# VCU_DV.net
KiCad netlist of a schematic drawn in Altium Designer
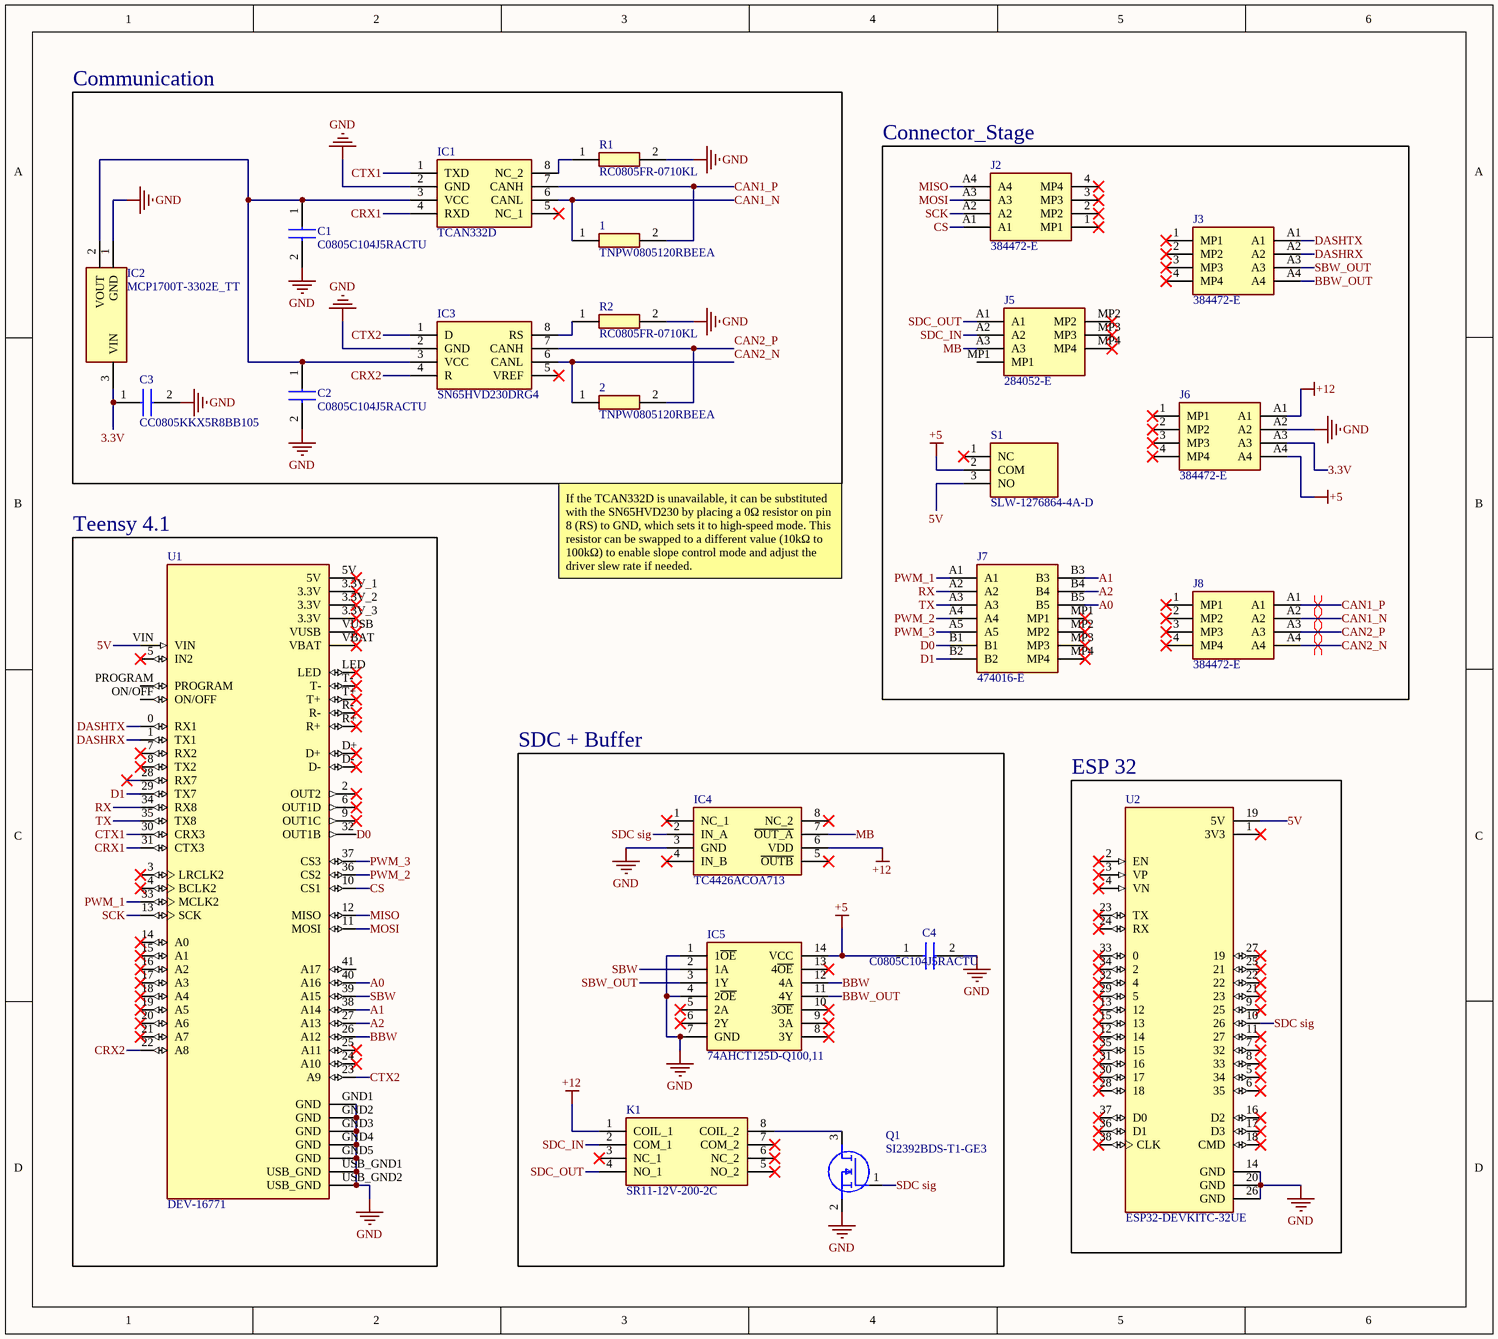
[diagram p0: VCU_DV.SchDoc]

(export (version "E")
  (design (tool "Eeschema 10.0.6"))
  (components
    (comp (ref "1")
      (value "TNPW0805120RBEEA")
      (footprint "SamacSys:RESC2012X55N")
      (description "Resistor")
      (fields (field (name "MOUSER PART NUMBER") "71-TNPW0805120RBEEA"))
      (libsource (lib "*") (part "TNPW0805120RBEEA"))
    )
    (comp (ref "2")
      (value "TNPW0805120RBEEA")
      (footprint "SamacSys:RESC2012X55N")
      (description "Resistor")
      (fields (field (name "MOUSER PART NUMBER") "71-TNPW0805120RBEEA"))
      (libsource (lib "*") (part "TNPW0805120RBEEA"))
    )
    (comp (ref "C1")
      (value "C0805C104J5RACTU")
      (footprint "SamacSys:C0805")
      (description "Capacitor")
      (fields (field (name "MOUSER PART NUMBER") "80-C0805C104J5R"))
      (libsource (lib "*") (part "C0805C104J5RACTU"))
    )
    (comp (ref "C2")
      (value "C0805C104J5RACTU")
      (footprint "SamacSys:C0805")
      (description "Capacitor")
      (fields (field (name "MOUSER PART NUMBER") "80-C0805C104J5R"))
      (libsource (lib "*") (part "C0805C104J5RACTU"))
    )
    (comp (ref "C3")
      (value "CC0805KKX5R8BB105")
      (footprint "SamacSys:CAPC2012X145N")
      (description "Capacitor")
      (fields (field (name "MOUSER PART NUMBER") "603-CC805KKX5R8BB105"))
      (libsource (lib "SamacSys") (part "CC0805KKX5R8BB105"))
    )
    (comp (ref "C4")
      (value "C0805C104J5RACTU")
      (footprint "SamacSys:C0805")
      (description "Capacitor")
      (fields (field (name "MOUSER PART NUMBER") "80-C0805C104J5R"))
      (libsource (lib "*") (part "C0805C104J5RACTU"))
    )
    (comp (ref "IC1")
      (value "TCAN332D")
      (footprint "SamacSys:TCAN332D")
      (description "Integrated Circuit")
      (fields (field (name "MOUSER PART NUMBER") "595-TCAN332D"))
      (libsource (lib "*") (part "TCAN332D"))
    )
    (comp (ref "IC2")
      (value "MCP1700T-3302E_TT")
      (footprint "SamacSys:SOT95P237X112-3N")
      (description "Integrated Circuit")
      (fields
        (field (name "MANUFACTURER_PART_NUMBER") "MCP1700T-3302E/TT")
        (field (name "MOUSER PART NUMBER") "579-MCP1700T3302E/TT")
      )
      (libsource (lib "*") (part "MCP1700T-3302E_TT"))
    )
    (comp (ref "IC3")
      (value "SN65HVD230DRG4")
      (footprint "SamacSys:SOIC127P600X175-8N")
      (description "Integrated Circuit")
      (fields (field (name "MOUSER PART NUMBER") "595-SN65HVD230DRG4"))
      (libsource (lib "*") (part "SN65HVD230DRG4"))
    )
    (comp (ref "IC4")
      (value "TC4426ACOA713")
      (footprint "SamacSys:SOIC127P600X175-8N")
      (description "Integrated Circuit")
      (fields (field (name "MOUSER PART NUMBER") "579-TC4426ACOA713"))
      (libsource (lib "*") (part "TC4426ACOA713"))
    )
    (comp (ref "IC5")
      (value "74AHCT125D-Q100,11")
      (footprint "SamacSys:SOIC127P600X175-14N")
      (description "Integrated Circuit")
      (fields (field (name "MOUSER PART NUMBER") "771-74AHCT100D-Q100"))
      (libsource (lib "*") (part "74AHCT125D-Q100,11"))
    )
    (comp (ref "J2")
      (value "384472-E")
      (footprint "SamacSys:384472E")
      (description "Connector")
      (libsource (lib "") (part "384472-E_1"))
    )
    (comp (ref "J3")
      (value "384472-E")
      (footprint "SamacSys:384472E")
      (description "Connector")
      (libsource (lib "*") (part "384472-E"))
    )
    (comp (ref "J5")
      (value "284052-E")
      (footprint "SamacSys:284052E")
      (description "Connector")
      (fields (field (name "MOUSER PART NUMBER") "305-284052"))
      (libsource (lib "SamacSys") (part "284052-E"))
    )
    (comp (ref "J6")
      (value "384472-E")
      (footprint "SamacSys:384472E")
      (description "Connector")
      (libsource (lib "*") (part "384472-E"))
    )
    (comp (ref "J7")
      (value "474016-E")
      (footprint "SamacSys:474016E")
      (description "Connector")
      (fields (field (name "MOUSER PART NUMBER") "305-474016"))
      (libsource (lib "*") (part "474016-E"))
    )
    (comp (ref "J8")
      (value "384472-E")
      (footprint "SamacSys:384472E")
      (description "Connector")
      (libsource (lib "*") (part "384472-E"))
    )
    (comp (ref "K1")
      (value "SR11-12V-200-2C")
      (footprint "SamacSys:SR1112V2002C")
      (description "Relay or Contactor")
      (fields (field (name "MOUSER PART NUMBER") "179-SR11-12V-200-2C"))
      (libsource (lib "*") (part "SR11-12V-200-2C"))
    )
    (comp (ref "Q1")
      (value "SI2392BDS-T1-GE3")
      (footprint "SamacSys:SOT95P237X112-3N")
      (description "MOSFET (N-Channel)")
      (fields (field (name "MOUSER PART NUMBER") "78-SI2392BDS"))
      (libsource (lib "SamacSys") (part "SI2392BDS-T1-GE3"))
    )
    (comp (ref "R1")
      (value "RC0805FR-0710KL")
      (footprint "SamacSys:RESC2012X60N")
      (description "Resistor")
      (fields (field (name "MOUSER PART NUMBER") "603-RC0805FR-0710KL"))
      (libsource (lib "SamacSys") (part "RC0805FR-0710KL"))
    )
    (comp (ref "R2")
      (value "RC0805FR-0710KL")
      (footprint "SamacSys:RESC2012X60N")
      (description "Resistor")
      (fields (field (name "MOUSER PART NUMBER") "603-RC0805FR-0710KL"))
      (libsource (lib "SamacSys") (part "RC0805FR-0710KL"))
    )
    (comp (ref "S1")
      (value "SLW-1276864-4A-D")
      (footprint "SamacSys:SLW12768644AD")
      (description "Switch")
      (fields (field (name "MOUSER PART NUMBER") "179-SLW-1276864-4A-D"))
      (libsource (lib "*") (part "SLW-1276864-4A-D"))
    )
    (comp (ref "U1")
      (value "DEV-16771")
      (footprint "MODULE_DEV-16771")
      (description "RT1062 Teensy 4.1 series ARM® Cortex®-M7 MPU Embedded Evaluation Board")
      (fields (field (name "MF") "SparkFun Electronics"))
      (libsource (lib "DEV-16771") (part "DEV-16771"))
    )
    (comp (ref "U2")
      (value "ESP32-DEVKITC-32UE")
      (footprint "ESPRESSIF_ESP32-DEVKITC-32UE")
      (fields (field (name "MF") "Espressif Systems"))
      (libsource (lib "ESP32-DEVKITC-32UE") (part "ESP32-DEVKITC-32UE"))
    )
  )
  (nets
    (net (code "1") (name "+5") (class "Default")
      (node (ref "C4") (pin "1") (pinfunction "1_1") (pintype "passive"))
      (node (ref "IC5") (pin "14") (pinfunction "VCC_14") (pintype "passive"))
      (node (ref "J6") (pin "A4") (pinfunction "A4_A4") (pintype "passive"))
      (node (ref "S1") (pin "2") (pinfunction "COM_2") (pintype "passive"))
    )
    (net (code "2") (name "+12") (class "Default")
      (node (ref "IC4") (pin "6") (pinfunction "VDD_6") (pintype "passive"))
      (node (ref "J6") (pin "A1") (pinfunction "A1_A1") (pintype "passive"))
      (node (ref "K1") (pin "1") (pinfunction "COIL_1_1") (pintype "passive"))
    )
    (net (code "3") (name "/3.3V") (class "Default")
      (node (ref "C3") (pin "1") (pinfunction "1_1") (pintype "passive"))
      (node (ref "IC2") (pin "3") (pinfunction "VIN_3") (pintype "passive"))
      (node (ref "J6") (pin "A3") (pinfunction "A3_A3") (pintype "passive"))
    )
    (net (code "4") (name "/5V") (class "Default")
      (node (ref "S1") (pin "3") (pinfunction "NO_3") (pintype "passive"))
      (node (ref "U1") (pin "VIN") (pinfunction "VIN_VIN") (pintype "input"))
      (node (ref "U2") (pin "19") (pinfunction "5V_19") (pintype "power_in"))
    )
    (net (code "5") (name "/A0") (class "Default")
      (node (ref "J7") (pin "B5") (pinfunction "B5_B5") (pintype "passive"))
      (node (ref "U1") (pin "40") (pinfunction "A16_40") (pintype "bidirectional"))
    )
    (net (code "6") (name "/A1") (class "Default")
      (node (ref "J7") (pin "B3") (pinfunction "B3_B3") (pintype "passive"))
      (node (ref "U1") (pin "38") (pinfunction "A14_38") (pintype "bidirectional"))
    )
    (net (code "7") (name "/A2") (class "Default")
      (node (ref "J7") (pin "B4") (pinfunction "B4_B4") (pintype "passive"))
      (node (ref "U1") (pin "27") (pinfunction "A13_27") (pintype "bidirectional"))
    )
    (net (code "8") (name "/BBW") (class "Default")
      (node (ref "IC5") (pin "12") (pinfunction "4A_12") (pintype "passive"))
      (node (ref "U1") (pin "26") (pinfunction "A12_26") (pintype "bidirectional"))
    )
    (net (code "9") (name "/BBW_OUT") (class "Default")
      (node (ref "IC5") (pin "11") (pinfunction "4Y_11") (pintype "passive"))
      (node (ref "J3") (pin "A4") (pinfunction "A4_A4") (pintype "passive"))
    )
    (net (code "10") (name "/CAN1_N") (class "Default")
      (node (ref "1") (pin "1") (pinfunction "1_1") (pintype "passive"))
      (node (ref "IC1") (pin "6") (pinfunction "CANL_6") (pintype "passive"))
      (node (ref "J8") (pin "A2") (pinfunction "A2_A2") (pintype "passive"))
    )
    (net (code "11") (name "/CAN1_P") (class "Default")
      (node (ref "1") (pin "2") (pinfunction "2_2") (pintype "passive"))
      (node (ref "IC1") (pin "7") (pinfunction "CANH_7") (pintype "passive"))
      (node (ref "J8") (pin "A1") (pinfunction "A1_A1") (pintype "passive"))
    )
    (net (code "12") (name "/CAN2_N") (class "Default")
      (node (ref "2") (pin "1") (pinfunction "1_1") (pintype "passive"))
      (node (ref "IC3") (pin "6") (pinfunction "CANL_6") (pintype "passive"))
      (node (ref "J8") (pin "A4") (pinfunction "A4_A4") (pintype "passive"))
    )
    (net (code "13") (name "/CAN2_P") (class "Default")
      (node (ref "2") (pin "2") (pinfunction "2_2") (pintype "passive"))
      (node (ref "IC3") (pin "7") (pinfunction "CANH_7") (pintype "passive"))
      (node (ref "J8") (pin "A3") (pinfunction "A3_A3") (pintype "passive"))
    )
    (net (code "14") (name "/CRX1") (class "Default")
      (node (ref "IC1") (pin "4") (pinfunction "RXD_4") (pintype "passive"))
      (node (ref "U1") (pin "31") (pinfunction "CTX3_31") (pintype "bidirectional"))
    )
    (net (code "15") (name "/CRX2") (class "Default")
      (node (ref "IC3") (pin "4") (pinfunction "R_4") (pintype "passive"))
      (node (ref "U1") (pin "22") (pinfunction "A8_22") (pintype "bidirectional"))
    )
    (net (code "16") (name "/CS") (class "Default")
      (node (ref "J2") (pin "A1") (pinfunction "A1_A1") (pintype "passive"))
      (node (ref "U1") (pin "10") (pinfunction "CS1_10") (pintype "bidirectional"))
    )
    (net (code "17") (name "/CTX1") (class "Default")
      (node (ref "IC1") (pin "1") (pinfunction "TXD_1") (pintype "passive"))
      (node (ref "U1") (pin "30") (pinfunction "CRX3_30") (pintype "bidirectional"))
    )
    (net (code "18") (name "/CTX2") (class "Default")
      (node (ref "IC3") (pin "1") (pinfunction "D_1") (pintype "passive"))
      (node (ref "U1") (pin "23") (pinfunction "A9_23") (pintype "bidirectional"))
    )
    (net (code "19") (name "/D0") (class "Default")
      (node (ref "J7") (pin "B1") (pinfunction "B1_B1") (pintype "passive"))
      (node (ref "U1") (pin "32") (pinfunction "OUT1B_32") (pintype "output"))
    )
    (net (code "20") (name "/D1") (class "Default")
      (node (ref "J7") (pin "B2") (pinfunction "B2_B2") (pintype "passive"))
      (node (ref "U1") (pin "29") (pinfunction "TX7_29") (pintype "bidirectional"))
    )
    (net (code "21") (name "/DASHRX") (class "Default")
      (node (ref "J3") (pin "A2") (pinfunction "A2_A2") (pintype "passive"))
      (node (ref "U1") (pin "1") (pinfunction "TX1_1") (pintype "bidirectional"))
    )
    (net (code "22") (name "/DASHTX") (class "Default")
      (node (ref "J3") (pin "A1") (pinfunction "A1_A1") (pintype "passive"))
      (node (ref "U1") (pin "0") (pinfunction "RX1_0") (pintype "bidirectional"))
    )
    (net (code "23") (name "/MB") (class "Default")
      (node (ref "IC4") (pin "7") (pinfunction "~{OUT_A}_7") (pintype "passive"))
      (node (ref "J5") (pin "A3") (pinfunction "A3_A3") (pintype "passive"))
    )
    (net (code "24") (name "/MISO") (class "Default")
      (node (ref "J2") (pin "A4") (pinfunction "A4_A4") (pintype "passive"))
      (node (ref "U1") (pin "12") (pinfunction "MISO_12") (pintype "bidirectional"))
    )
    (net (code "25") (name "/MOSI") (class "Default")
      (node (ref "J2") (pin "A3") (pinfunction "A3_A3") (pintype "passive"))
      (node (ref "U1") (pin "11") (pinfunction "MOSI_11") (pintype "bidirectional"))
    )
    (net (code "26") (name "/PWM_1") (class "Default")
      (node (ref "J7") (pin "A1") (pinfunction "A1_A1") (pintype "passive"))
      (node (ref "U1") (pin "33") (pinfunction "MCLK2_33") (pintype "bidirectional"))
    )
    (net (code "27") (name "/PWM_2") (class "Default")
      (node (ref "J7") (pin "A4") (pinfunction "A4_A4") (pintype "passive"))
      (node (ref "U1") (pin "36") (pinfunction "CS2_36") (pintype "bidirectional"))
    )
    (net (code "28") (name "/PWM_3") (class "Default")
      (node (ref "J7") (pin "A5") (pinfunction "A5_A5") (pintype "passive"))
      (node (ref "U1") (pin "37") (pinfunction "CS3_37") (pintype "bidirectional"))
    )
    (net (code "29") (name "/RX") (class "Default")
      (node (ref "J7") (pin "A2") (pinfunction "A2_A2") (pintype "passive"))
      (node (ref "U1") (pin "34") (pinfunction "RX8_34") (pintype "bidirectional"))
    )
    (net (code "30") (name "/SBW") (class "Default")
      (node (ref "IC5") (pin "2") (pinfunction "1A_2") (pintype "passive"))
      (node (ref "U1") (pin "39") (pinfunction "A15_39") (pintype "bidirectional"))
    )
    (net (code "31") (name "/SBW_OUT") (class "Default")
      (node (ref "IC5") (pin "3") (pinfunction "1Y_3") (pintype "passive"))
      (node (ref "J3") (pin "A3") (pinfunction "A3_A3") (pintype "passive"))
    )
    (net (code "32") (name "/SCK") (class "Default")
      (node (ref "J2") (pin "A2") (pinfunction "A2_A2") (pintype "passive"))
      (node (ref "U1") (pin "13") (pinfunction "SCK_13") (pintype "bidirectional"))
    )
    (net (code "33") (name "/SDC sig") (class "Default")
      (node (ref "IC4") (pin "2") (pinfunction "IN_A_2") (pintype "passive"))
      (node (ref "Q1") (pin "1") (pinfunction "G_1") (pintype "passive"))
      (node (ref "U2") (pin "10") (pinfunction "26_10") (pintype "bidirectional"))
    )
    (net (code "34") (name "/SDC_IN") (class "Default")
      (node (ref "J5") (pin "A2") (pinfunction "A2_A2") (pintype "passive"))
      (node (ref "K1") (pin "2") (pinfunction "COM_1_2") (pintype "passive"))
    )
    (net (code "35") (name "/SDC_OUT") (class "Default")
      (node (ref "J5") (pin "A1") (pinfunction "A1_A1") (pintype "passive"))
      (node (ref "K1") (pin "4") (pinfunction "NO_1_4") (pintype "passive"))
    )
    (net (code "36") (name "/TX") (class "Default")
      (node (ref "J7") (pin "A3") (pinfunction "A3_A3") (pintype "passive"))
      (node (ref "U1") (pin "35") (pinfunction "TX8_35") (pintype "bidirectional"))
    )
    (net (code "37") (name "GND") (class "Default")
      (node (ref "C1") (pin "2") (pinfunction "2_2") (pintype "passive"))
      (node (ref "C2") (pin "2") (pinfunction "2_2") (pintype "passive"))
      (node (ref "C3") (pin "2") (pinfunction "2_2") (pintype "passive"))
      (node (ref "C4") (pin "2") (pinfunction "2_2") (pintype "passive"))
      (node (ref "IC1") (pin "2") (pinfunction "GND_2") (pintype "passive"))
      (node (ref "IC2") (pin "1") (pinfunction "GND_1") (pintype "passive"))
      (node (ref "IC3") (pin "2") (pinfunction "GND_2") (pintype "passive"))
      (node (ref "IC4") (pin "3") (pinfunction "GND_3") (pintype "passive"))
      (node (ref "IC5") (pin "1") (pinfunction "1~{OE}_1") (pintype "passive"))
      (node (ref "IC5") (pin "4") (pinfunction "2~{OE}_4") (pintype "passive"))
      (node (ref "IC5") (pin "7") (pinfunction "GND_7") (pintype "passive"))
      (node (ref "J6") (pin "A2") (pinfunction "A2_A2") (pintype "passive"))
      (node (ref "Q1") (pin "2") (pinfunction "S_2") (pintype "passive"))
      (node (ref "R1") (pin "2") (pinfunction "2_2") (pintype "passive"))
      (node (ref "R2") (pin "2") (pinfunction "2_2") (pintype "passive"))
      (node (ref "U1") (pin "GND1") (pinfunction "GND_GND1") (pintype "power_in"))
      (node (ref "U1") (pin "GND2") (pinfunction "GND_GND2") (pintype "power_in"))
      (node (ref "U1") (pin "GND3") (pinfunction "GND_GND3") (pintype "power_in"))
      (node (ref "U1") (pin "GND4") (pinfunction "GND_GND4") (pintype "power_in"))
      (node (ref "U1") (pin "GND5") (pinfunction "GND_GND5") (pintype "power_in"))
      (node (ref "U1") (pin "USB_GND1") (pinfunction "USB_GND_USB_GND1") (pintype "power_in"))
      (node (ref "U1") (pin "USB_GND2") (pinfunction "USB_GND_USB_GND2") (pintype "power_in"))
      (node (ref "U2") (pin "14") (pinfunction "GND_14") (pintype "power_in"))
      (node (ref "U2") (pin "20") (pinfunction "GND_20") (pintype "power_in"))
      (node (ref "U2") (pin "26") (pinfunction "GND_26") (pintype "power_in"))
    )
    (net (code "38") (name "Net-(IC1-NC_2)") (class "Default")
      (node (ref "IC1") (pin "8") (pinfunction "NC_2_8") (pintype "passive"))
      (node (ref "R1") (pin "1") (pinfunction "1_1") (pintype "passive"))
    )
    (net (code "39") (name "Net-(IC1-VCC)") (class "Default")
      (node (ref "C1") (pin "1") (pinfunction "1_1") (pintype "passive"))
      (node (ref "C2") (pin "1") (pinfunction "1_1") (pintype "passive"))
      (node (ref "IC1") (pin "3") (pinfunction "VCC_3") (pintype "passive"))
      (node (ref "IC2") (pin "2") (pinfunction "VOUT_2") (pintype "passive"))
      (node (ref "IC3") (pin "3") (pinfunction "VCC_3") (pintype "passive"))
    )
    (net (code "40") (name "Net-(IC3-RS)") (class "Default")
      (node (ref "IC3") (pin "8") (pinfunction "RS_8") (pintype "passive"))
      (node (ref "R2") (pin "1") (pinfunction "1_1") (pintype "passive"))
    )
    (net (code "41") (name "Net-(K1-COIL_2)") (class "Default")
      (node (ref "K1") (pin "8") (pinfunction "COIL_2_8") (pintype "passive"))
      (node (ref "Q1") (pin "3") (pinfunction "D_3") (pintype "passive"))
    )
    (net (code "42") (name "unconnected-(IC1-NC_1-Pad5)") (class "Default")
      (node (ref "IC1") (pin "5") (pinfunction "NC_1_5") (pintype "passive+no_connect"))
    )
    (net (code "43") (name "unconnected-(IC3-VREF-Pad5)") (class "Default")
      (node (ref "IC3") (pin "5") (pinfunction "VREF_5") (pintype "passive+no_connect"))
    )
    (net (code "44") (name "unconnected-(IC4-IN_B-Pad4)") (class "Default")
      (node (ref "IC4") (pin "4") (pinfunction "IN_B_4") (pintype "passive+no_connect"))
    )
    (net (code "45") (name "unconnected-(IC4-NC_1-Pad1)") (class "Default")
      (node (ref "IC4") (pin "1") (pinfunction "NC_1_1") (pintype "passive+no_connect"))
    )
    (net (code "46") (name "unconnected-(IC4-NC_2-Pad8)") (class "Default")
      (node (ref "IC4") (pin "8") (pinfunction "NC_2_8") (pintype "passive+no_connect"))
    )
    (net (code "47") (name "unconnected-(IC4-~{OUTB}-Pad5)") (class "Default")
      (node (ref "IC4") (pin "5") (pinfunction "~{OUTB}_5") (pintype "passive+no_connect"))
    )
    (net (code "48") (name "unconnected-(IC5-2A-Pad5)") (class "Default")
      (node (ref "IC5") (pin "5") (pinfunction "2A_5") (pintype "passive+no_connect"))
    )
    (net (code "49") (name "unconnected-(IC5-2Y-Pad6)") (class "Default")
      (node (ref "IC5") (pin "6") (pinfunction "2Y_6") (pintype "passive+no_connect"))
    )
    (net (code "50") (name "unconnected-(IC5-3A-Pad9)") (class "Default")
      (node (ref "IC5") (pin "9") (pinfunction "3A_9") (pintype "passive+no_connect"))
    )
    (net (code "51") (name "unconnected-(IC5-3Y-Pad8)") (class "Default")
      (node (ref "IC5") (pin "8") (pinfunction "3Y_8") (pintype "passive+no_connect"))
    )
    (net (code "52") (name "unconnected-(IC5-3~{OE}-Pad10)") (class "Default")
      (node (ref "IC5") (pin "10") (pinfunction "3~{OE}_10") (pintype "passive+no_connect"))
    )
    (net (code "53") (name "unconnected-(IC5-4~{OE}-Pad13)") (class "Default")
      (node (ref "IC5") (pin "13") (pinfunction "4~{OE}_13") (pintype "passive+no_connect"))
    )
    (net (code "54") (name "unconnected-(J2-MP1-Pad1)") (class "Default")
      (node (ref "J2") (pin "1") (pinfunction "MP1_1") (pintype "passive+no_connect"))
    )
    (net (code "55") (name "unconnected-(J2-MP2-Pad2)") (class "Default")
      (node (ref "J2") (pin "2") (pinfunction "MP2_2") (pintype "passive+no_connect"))
    )
    (net (code "56") (name "unconnected-(J2-MP3-Pad3)") (class "Default")
      (node (ref "J2") (pin "3") (pinfunction "MP3_3") (pintype "passive+no_connect"))
    )
    (net (code "57") (name "unconnected-(J2-MP4-Pad4)") (class "Default")
      (node (ref "J2") (pin "4") (pinfunction "MP4_4") (pintype "passive+no_connect"))
    )
    (net (code "58") (name "unconnected-(J3-MP1-Pad1)") (class "Default")
      (node (ref "J3") (pin "1") (pinfunction "MP1_1") (pintype "passive+no_connect"))
    )
    (net (code "59") (name "unconnected-(J3-MP2-Pad2)") (class "Default")
      (node (ref "J3") (pin "2") (pinfunction "MP2_2") (pintype "passive+no_connect"))
    )
    (net (code "60") (name "unconnected-(J3-MP3-Pad3)") (class "Default")
      (node (ref "J3") (pin "3") (pinfunction "MP3_3") (pintype "passive+no_connect"))
    )
    (net (code "61") (name "unconnected-(J3-MP4-Pad4)") (class "Default")
      (node (ref "J3") (pin "4") (pinfunction "MP4_4") (pintype "passive+no_connect"))
    )
    (net (code "62") (name "unconnected-(J5-PadMP1)") (class "Default")
      (node (ref "J5") (pin "MP1") (pinfunction "MP1_MP1") (pintype "passive"))
    )
    (net (code "63") (name "unconnected-(J5-PadMP2)") (class "Default")
      (node (ref "J5") (pin "MP2") (pinfunction "MP2_MP2") (pintype "passive+no_connect"))
    )
    (net (code "64") (name "unconnected-(J5-PadMP3)") (class "Default")
      (node (ref "J5") (pin "MP3") (pinfunction "MP3_MP3") (pintype "passive+no_connect"))
    )
    (net (code "65") (name "unconnected-(J5-PadMP4)") (class "Default")
      (node (ref "J5") (pin "MP4") (pinfunction "MP4_MP4") (pintype "passive+no_connect"))
    )
    (net (code "66") (name "unconnected-(J6-MP1-Pad1)") (class "Default")
      (node (ref "J6") (pin "1") (pinfunction "MP1_1") (pintype "passive+no_connect"))
    )
    (net (code "67") (name "unconnected-(J6-MP2-Pad2)") (class "Default")
      (node (ref "J6") (pin "2") (pinfunction "MP2_2") (pintype "passive+no_connect"))
    )
    (net (code "68") (name "unconnected-(J6-MP3-Pad3)") (class "Default")
      (node (ref "J6") (pin "3") (pinfunction "MP3_3") (pintype "passive+no_connect"))
    )
    (net (code "69") (name "unconnected-(J6-MP4-Pad4)") (class "Default")
      (node (ref "J6") (pin "4") (pinfunction "MP4_4") (pintype "passive+no_connect"))
    )
    (net (code "70") (name "unconnected-(J7-PadMP1)") (class "Default")
      (node (ref "J7") (pin "MP1") (pinfunction "MP1_MP1") (pintype "passive+no_connect"))
    )
    (net (code "71") (name "unconnected-(J7-PadMP2)") (class "Default")
      (node (ref "J7") (pin "MP2") (pinfunction "MP2_MP2") (pintype "passive+no_connect"))
    )
    (net (code "72") (name "unconnected-(J7-PadMP3)") (class "Default")
      (node (ref "J7") (pin "MP3") (pinfunction "MP3_MP3") (pintype "passive+no_connect"))
    )
    (net (code "73") (name "unconnected-(J7-PadMP4)") (class "Default")
      (node (ref "J7") (pin "MP4") (pinfunction "MP4_MP4") (pintype "passive+no_connect"))
    )
    (net (code "74") (name "unconnected-(J8-MP1-Pad1)") (class "Default")
      (node (ref "J8") (pin "1") (pinfunction "MP1_1") (pintype "passive+no_connect"))
    )
    (net (code "75") (name "unconnected-(J8-MP2-Pad2)") (class "Default")
      (node (ref "J8") (pin "2") (pinfunction "MP2_2") (pintype "passive+no_connect"))
    )
    (net (code "76") (name "unconnected-(J8-MP3-Pad3)") (class "Default")
      (node (ref "J8") (pin "3") (pinfunction "MP3_3") (pintype "passive+no_connect"))
    )
    (net (code "77") (name "unconnected-(J8-MP4-Pad4)") (class "Default")
      (node (ref "J8") (pin "4") (pinfunction "MP4_4") (pintype "passive+no_connect"))
    )
    (net (code "78") (name "unconnected-(K1-COM_2-Pad7)") (class "Default")
      (node (ref "K1") (pin "7") (pinfunction "COM_2_7") (pintype "passive+no_connect"))
    )
    (net (code "79") (name "unconnected-(K1-NC_1-Pad3)") (class "Default")
      (node (ref "K1") (pin "3") (pinfunction "NC_1_3") (pintype "passive+no_connect"))
    )
    (net (code "80") (name "unconnected-(K1-NC_2-Pad6)") (class "Default")
      (node (ref "K1") (pin "6") (pinfunction "NC_2_6") (pintype "passive+no_connect"))
    )
    (net (code "81") (name "unconnected-(K1-NO_2-Pad5)") (class "Default")
      (node (ref "K1") (pin "5") (pinfunction "NO_2_5") (pintype "passive+no_connect"))
    )
    (net (code "82") (name "unconnected-(S1-NC-Pad1)") (class "Default")
      (node (ref "S1") (pin "1") (pinfunction "NC_1") (pintype "passive+no_connect"))
    )
    (net (code "83") (name "unconnected-(U1-3.3V-Pad3.3V_1)") (class "Default")
      (node (ref "U1") (pin "3.3V_1") (pinfunction "3.3V_3.3V_1") (pintype "power_in+no_connect"))
    )
    (net (code "84") (name "unconnected-(U1-3.3V-Pad3.3V_2)") (class "Default")
      (node (ref "U1") (pin "3.3V_2") (pinfunction "3.3V_3.3V_2") (pintype "power_in+no_connect"))
    )
    (net (code "85") (name "unconnected-(U1-3.3V-Pad3.3V_3)") (class "Default")
      (node (ref "U1") (pin "3.3V_3") (pinfunction "3.3V_3.3V_3") (pintype "power_in+no_connect"))
    )
    (net (code "86") (name "unconnected-(U1-A0-Pad14)") (class "Default")
      (node (ref "U1") (pin "14") (pinfunction "A0_14") (pintype "bidirectional+no_connect"))
    )
    (net (code "87") (name "unconnected-(U1-A1-Pad15)") (class "Default")
      (node (ref "U1") (pin "15") (pinfunction "A1_15") (pintype "bidirectional+no_connect"))
    )
    (net (code "88") (name "unconnected-(U1-A2-Pad16)") (class "Default")
      (node (ref "U1") (pin "16") (pinfunction "A2_16") (pintype "bidirectional+no_connect"))
    )
    (net (code "89") (name "unconnected-(U1-A3-Pad17)") (class "Default")
      (node (ref "U1") (pin "17") (pinfunction "A3_17") (pintype "bidirectional+no_connect"))
    )
    (net (code "90") (name "unconnected-(U1-A4-Pad18)") (class "Default")
      (node (ref "U1") (pin "18") (pinfunction "A4_18") (pintype "bidirectional+no_connect"))
    )
    (net (code "91") (name "unconnected-(U1-A5-Pad19)") (class "Default")
      (node (ref "U1") (pin "19") (pinfunction "A5_19") (pintype "bidirectional+no_connect"))
    )
    (net (code "92") (name "unconnected-(U1-A6-Pad20)") (class "Default")
      (node (ref "U1") (pin "20") (pinfunction "A6_20") (pintype "bidirectional+no_connect"))
    )
    (net (code "93") (name "unconnected-(U1-A7-Pad21)") (class "Default")
      (node (ref "U1") (pin "21") (pinfunction "A7_21") (pintype "bidirectional+no_connect"))
    )
    (net (code "94") (name "unconnected-(U1-A10-Pad24)") (class "Default")
      (node (ref "U1") (pin "24") (pinfunction "A10_24") (pintype "bidirectional+no_connect"))
    )
    (net (code "95") (name "unconnected-(U1-A11-Pad25)") (class "Default")
      (node (ref "U1") (pin "25") (pinfunction "A11_25") (pintype "bidirectional+no_connect"))
    )
    (net (code "96") (name "unconnected-(U1-A17-Pad41)") (class "Default")
      (node (ref "U1") (pin "41") (pinfunction "A17_41") (pintype "bidirectional"))
    )
    (net (code "97") (name "unconnected-(U1-BCLK2-Pad4)") (class "Default")
      (node (ref "U1") (pin "4") (pinfunction "BCLK2_4") (pintype "bidirectional+no_connect"))
    )
    (net (code "98") (name "unconnected-(U1-IN2-Pad5)") (class "Default")
      (node (ref "U1") (pin "5") (pinfunction "IN2_5") (pintype "bidirectional+no_connect"))
    )
    (net (code "99") (name "unconnected-(U1-LRCLK2-Pad3)") (class "Default")
      (node (ref "U1") (pin "3") (pinfunction "LRCLK2_3") (pintype "bidirectional+no_connect"))
    )
    (net (code "100") (name "unconnected-(U1-OUT1C-Pad9)") (class "Default")
      (node (ref "U1") (pin "9") (pinfunction "OUT1C_9") (pintype "output+no_connect"))
    )
    (net (code "101") (name "unconnected-(U1-OUT1D-Pad6)") (class "Default")
      (node (ref "U1") (pin "6") (pinfunction "OUT1D_6") (pintype "output+no_connect"))
    )
    (net (code "102") (name "unconnected-(U1-OUT2-Pad2)") (class "Default")
      (node (ref "U1") (pin "2") (pinfunction "OUT2_2") (pintype "output+no_connect"))
    )
    (net (code "103") (name "unconnected-(U1-Pad5V)") (class "Default")
      (node (ref "U1") (pin "5V") (pinfunction "5V_5V") (pintype "power_in+no_connect"))
    )
    (net (code "104") (name "unconnected-(U1-PadD+)") (class "Default")
      (node (ref "U1") (pin "D+") (pinfunction "D+_D+") (pintype "bidirectional+no_connect"))
    )
    (net (code "105") (name "unconnected-(U1-PadD-)") (class "Default")
      (node (ref "U1") (pin "D-") (pinfunction "D-_D-") (pintype "bidirectional+no_connect"))
    )
    (net (code "106") (name "unconnected-(U1-PadLED)") (class "Default")
      (node (ref "U1") (pin "LED") (pinfunction "LED_LED") (pintype "bidirectional+no_connect"))
    )
    (net (code "107") (name "unconnected-(U1-PadON{slash}OFF)") (class "Default")
      (node (ref "U1") (pin "ON/OFF") (pinfunction "ON/OFF_ON/OFF") (pintype "bidirectional"))
    )
    (net (code "108") (name "unconnected-(U1-PadPROGRAM)") (class "Default")
      (node (ref "U1") (pin "PROGRAM") (pinfunction "PROGRAM_PROGRAM") (pintype "bidirectional"))
    )
    (net (code "109") (name "unconnected-(U1-PadR+)") (class "Default")
      (node (ref "U1") (pin "R+") (pinfunction "R+_R+") (pintype "bidirectional+no_connect"))
    )
    (net (code "110") (name "unconnected-(U1-PadR-)") (class "Default")
      (node (ref "U1") (pin "R-") (pinfunction "R-_R-") (pintype "bidirectional+no_connect"))
    )
    (net (code "111") (name "unconnected-(U1-PadT+)") (class "Default")
      (node (ref "U1") (pin "T+") (pinfunction "T+_T+") (pintype "bidirectional+no_connect"))
    )
    (net (code "112") (name "unconnected-(U1-PadT-)") (class "Default")
      (node (ref "U1") (pin "T-") (pinfunction "T-_T-") (pintype "bidirectional+no_connect"))
    )
    (net (code "113") (name "unconnected-(U1-PadVBAT)") (class "Default")
      (node (ref "U1") (pin "VBAT") (pinfunction "VBAT_VBAT") (pintype "passive+no_connect"))
    )
    (net (code "114") (name "unconnected-(U1-PadVUSB)") (class "Default")
      (node (ref "U1") (pin "VUSB") (pinfunction "VUSB_VUSB") (pintype "passive+no_connect"))
    )
    (net (code "115") (name "unconnected-(U1-RX2-Pad7)") (class "Default")
      (node (ref "U1") (pin "7") (pinfunction "RX2_7") (pintype "bidirectional+no_connect"))
    )
    (net (code "116") (name "unconnected-(U1-RX7-Pad28)") (class "Default")
      (node (ref "U1") (pin "28") (pinfunction "RX7_28") (pintype "bidirectional+no_connect"))
    )
    (net (code "117") (name "unconnected-(U1-TX2-Pad8)") (class "Default")
      (node (ref "U1") (pin "8") (pinfunction "TX2_8") (pintype "bidirectional+no_connect"))
    )
    (net (code "118") (name "unconnected-(U2-0-Pad33)") (class "Default")
      (node (ref "U2") (pin "33") (pinfunction "0_33") (pintype "bidirectional+no_connect"))
    )
    (net (code "119") (name "unconnected-(U2-2-Pad34)") (class "Default")
      (node (ref "U2") (pin "34") (pinfunction "2_34") (pintype "bidirectional+no_connect"))
    )
    (net (code "120") (name "unconnected-(U2-3V3-Pad1)") (class "Default")
      (node (ref "U2") (pin "1") (pinfunction "3V3_1") (pintype "power_in+no_connect"))
    )
    (net (code "121") (name "unconnected-(U2-4-Pad32)") (class "Default")
      (node (ref "U2") (pin "32") (pinfunction "4_32") (pintype "bidirectional+no_connect"))
    )
    (net (code "122") (name "unconnected-(U2-5-Pad29)") (class "Default")
      (node (ref "U2") (pin "29") (pinfunction "5_29") (pintype "bidirectional+no_connect"))
    )
    (net (code "123") (name "unconnected-(U2-12-Pad13)") (class "Default")
      (node (ref "U2") (pin "13") (pinfunction "12_13") (pintype "bidirectional+no_connect"))
    )
    (net (code "124") (name "unconnected-(U2-13-Pad15)") (class "Default")
      (node (ref "U2") (pin "15") (pinfunction "13_15") (pintype "bidirectional+no_connect"))
    )
    (net (code "125") (name "unconnected-(U2-14-Pad12)") (class "Default")
      (node (ref "U2") (pin "12") (pinfunction "14_12") (pintype "bidirectional+no_connect"))
    )
    (net (code "126") (name "unconnected-(U2-15-Pad35)") (class "Default")
      (node (ref "U2") (pin "35") (pinfunction "15_35") (pintype "bidirectional+no_connect"))
    )
    (net (code "127") (name "unconnected-(U2-16-Pad31)") (class "Default")
      (node (ref "U2") (pin "31") (pinfunction "16_31") (pintype "bidirectional+no_connect"))
    )
    (net (code "128") (name "unconnected-(U2-17-Pad30)") (class "Default")
      (node (ref "U2") (pin "30") (pinfunction "17_30") (pintype "bidirectional+no_connect"))
    )
    (net (code "129") (name "unconnected-(U2-18-Pad28)") (class "Default")
      (node (ref "U2") (pin "28") (pinfunction "18_28") (pintype "bidirectional+no_connect"))
    )
    (net (code "130") (name "unconnected-(U2-19-Pad27)") (class "Default")
      (node (ref "U2") (pin "27") (pinfunction "19_27") (pintype "bidirectional+no_connect"))
    )
    (net (code "131") (name "unconnected-(U2-21-Pad25)") (class "Default")
      (node (ref "U2") (pin "25") (pinfunction "21_25") (pintype "bidirectional+no_connect"))
    )
    (net (code "132") (name "unconnected-(U2-23-Pad21)") (class "Default")
      (node (ref "U2") (pin "21") (pinfunction "23_21") (pintype "bidirectional+no_connect"))
    )
    (net (code "133") (name "unconnected-(U2-25-Pad9)") (class "Default")
      (node (ref "U2") (pin "9") (pinfunction "25_9") (pintype "bidirectional+no_connect"))
    )
    (net (code "134") (name "unconnected-(U2-27-Pad11)") (class "Default")
      (node (ref "U2") (pin "11") (pinfunction "27_11") (pintype "bidirectional+no_connect"))
    )
    (net (code "135") (name "unconnected-(U2-32-Pad7)") (class "Default")
      (node (ref "U2") (pin "7") (pinfunction "32_7") (pintype "bidirectional+no_connect"))
    )
    (net (code "136") (name "unconnected-(U2-33-Pad8)") (class "Default")
      (node (ref "U2") (pin "8") (pinfunction "33_8") (pintype "bidirectional+no_connect"))
    )
    (net (code "137") (name "unconnected-(U2-34-Pad5)") (class "Default")
      (node (ref "U2") (pin "5") (pinfunction "34_5") (pintype "bidirectional+no_connect"))
    )
    (net (code "138") (name "unconnected-(U2-35-Pad6)") (class "Default")
      (node (ref "U2") (pin "6") (pinfunction "35_6") (pintype "bidirectional+no_connect"))
    )
    (net (code "139") (name "unconnected-(U2-CLK-Pad38)") (class "Default")
      (node (ref "U2") (pin "38") (pinfunction "CLK_38") (pintype "bidirectional+no_connect"))
    )
    (net (code "140") (name "unconnected-(U2-CMD-Pad18)") (class "Default")
      (node (ref "U2") (pin "18") (pinfunction "CMD_18") (pintype "bidirectional+no_connect"))
    )
    (net (code "141") (name "unconnected-(U2-D0-Pad37)") (class "Default")
      (node (ref "U2") (pin "37") (pinfunction "D0_37") (pintype "bidirectional+no_connect"))
    )
    (net (code "142") (name "unconnected-(U2-D1-Pad36)") (class "Default")
      (node (ref "U2") (pin "36") (pinfunction "D1_36") (pintype "bidirectional+no_connect"))
    )
    (net (code "143") (name "unconnected-(U2-D2-Pad16)") (class "Default")
      (node (ref "U2") (pin "16") (pinfunction "D2_16") (pintype "bidirectional+no_connect"))
    )
    (net (code "144") (name "unconnected-(U2-D3-Pad17)") (class "Default")
      (node (ref "U2") (pin "17") (pinfunction "D3_17") (pintype "bidirectional+no_connect"))
    )
    (net (code "145") (name "unconnected-(U2-EN-Pad2)") (class "Default")
      (node (ref "U2") (pin "2") (pinfunction "EN_2") (pintype "input+no_connect"))
    )
    (net (code "146") (name "unconnected-(U2-Pad22)") (class "Default")
      (node (ref "U2") (pin "22") (pinfunction "22_22") (pintype "bidirectional+no_connect"))
    )
    (net (code "147") (name "unconnected-(U2-RX-Pad24)") (class "Default")
      (node (ref "U2") (pin "24") (pinfunction "RX_24") (pintype "bidirectional+no_connect"))
    )
    (net (code "148") (name "unconnected-(U2-TX-Pad23)") (class "Default")
      (node (ref "U2") (pin "23") (pinfunction "TX_23") (pintype "bidirectional+no_connect"))
    )
    (net (code "149") (name "unconnected-(U2-VN-Pad4)") (class "Default")
      (node (ref "U2") (pin "4") (pinfunction "VN_4") (pintype "input+no_connect"))
    )
    (net (code "150") (name "unconnected-(U2-VP-Pad3)") (class "Default")
      (node (ref "U2") (pin "3") (pinfunction "VP_3") (pintype "input+no_connect"))
    )
  )
)
